# PowerSwitchV1.net
KiCad netlist of a schematic drawn in EAGLE
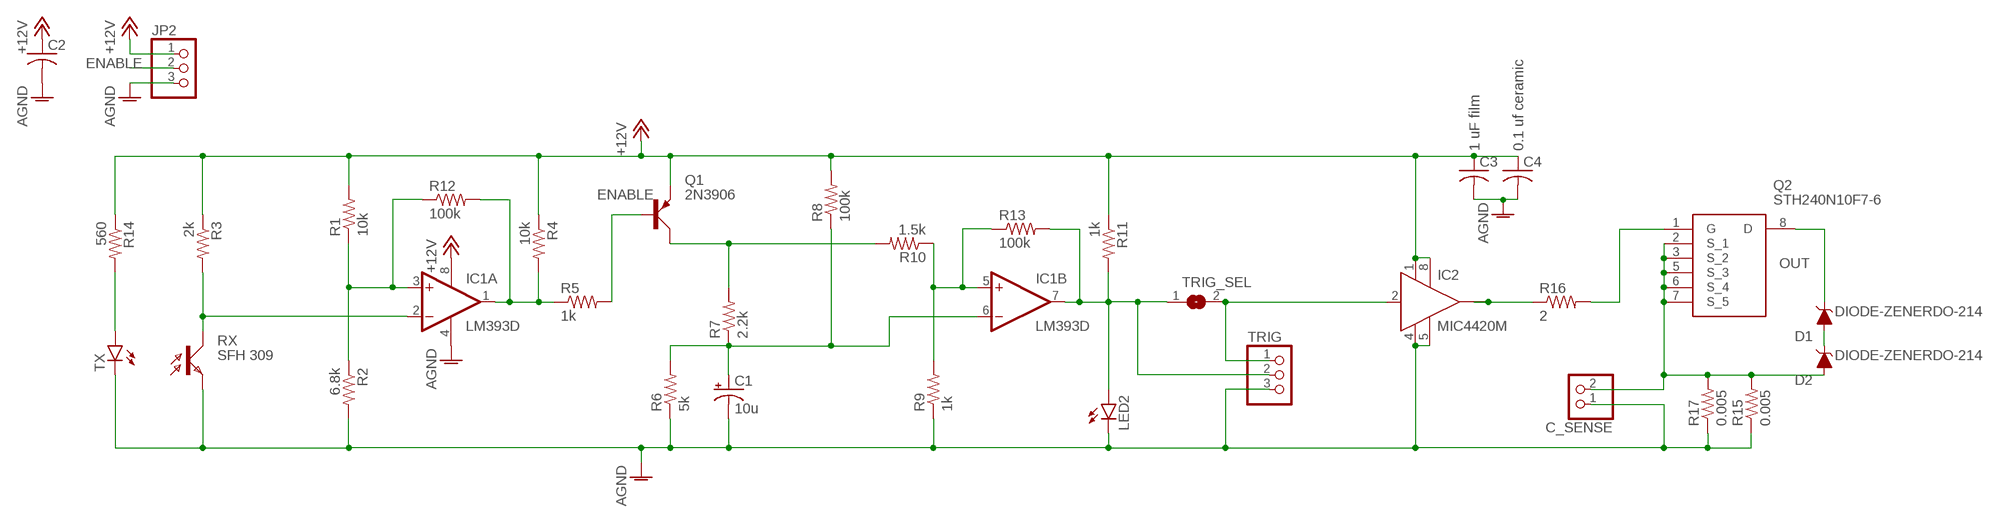
[diagram p0: schematic, sheet 1]

(export (version "E")
  (design (tool "Eeschema 10.0.6"))
  (components
    (comp (ref "C1")
      (value "10u")
      (footprint "eagle-import:TT2D6")
      (libsource (lib "eagle-import") (part "CPOL-USTT2D6"))
    )
    (comp (ref "C2")
      (value "C-US050-050X075")
      (footprint "eagle-import:C050-050X075")
      (libsource (lib "eagle-import") (part "C-US050-050X075"))
    )
    (comp (ref "C3")
      (value "1 uF film")
      (footprint "eagle-import:C050-045X075")
      (libsource (lib "eagle-import") (part "C-US050-045X075"))
    )
    (comp (ref "C4")
      (value "0.1 uf ceramic")
      (footprint "eagle-import:C025-030X050")
      (libsource (lib "eagle-import") (part "C-US025-030X050"))
    )
    (comp (ref "C_SENSE")
      (value "PINHD-1X2")
      (footprint "eagle-import:1X02")
      (libsource (lib "eagle-import") (part "PINHD-1X2"))
    )
    (comp (ref "D1")
      (value "DIODE-ZENERDO-214")
      (footprint "eagle-import:SMA-DIODE")
      (libsource (lib "eagle-import") (part "DIODE-ZENERDO-214"))
    )
    (comp (ref "D2")
      (value "DIODE-ZENERDO-214")
      (footprint "eagle-import:SMA-DIODE")
      (libsource (lib "eagle-import") (part "DIODE-ZENERDO-214"))
    )
    (comp (ref "IC1")
      (value "LM393D")
      (footprint "eagle-import:SO08")
      (libsource (lib "eagle-import") (part "LM393D"))
    )
    (comp (ref "IC2")
      (value "MIC4420M")
      (footprint "eagle-import:SO-08")
      (libsource (lib "eagle-import") (part "MIC4420M"))
    )
    (comp (ref "JP2")
      (value "PINHD-1X3")
      (footprint "eagle-import:1X03")
      (libsource (lib "eagle-import") (part "PINHD-1X3"))
    )
    (comp (ref "LED2")
      (value "LEDCHIPLED_0603")
      (footprint "eagle-import:CHIPLED_0603")
      (libsource (lib "eagle-import") (part "LEDCHIPLED_0603"))
    )
    (comp (ref "Q1")
      (value "2N3906")
      (footprint "eagle-import:TO92D")
      (libsource (lib "eagle-import") (part "2N3906"))
    )
    (comp (ref "Q2")
      (value "STH240N10F7-6")
      (footprint "eagle-import:H2PAK-6_1")
      (fields (field (name "MOUSER_PART_NUMBER") "511-STH240N10F7-6"))
      (libsource (lib "eagle-import") (part "STH240N10F7-6"))
    )
    (comp (ref "R1")
      (value "10k")
      (footprint "eagle-import:R0603")
      (libsource (lib "eagle-import") (part "R-US_R0603"))
    )
    (comp (ref "R2")
      (value "6.8k")
      (footprint "eagle-import:R0603")
      (libsource (lib "eagle-import") (part "R-US_R0603"))
    )
    (comp (ref "R3")
      (value "2k")
      (footprint "eagle-import:R0603")
      (libsource (lib "eagle-import") (part "R-US_R0603"))
    )
    (comp (ref "R4")
      (value "10k")
      (footprint "eagle-import:R0603")
      (libsource (lib "eagle-import") (part "R-US_R0603"))
    )
    (comp (ref "R5")
      (value "1k")
      (footprint "eagle-import:R0603")
      (libsource (lib "eagle-import") (part "R-US_R0603"))
    )
    (comp (ref "R6")
      (value "5k")
      (footprint "eagle-import:R0603")
      (libsource (lib "eagle-import") (part "R-US_R0603"))
    )
    (comp (ref "R7")
      (value "2.2k")
      (footprint "eagle-import:R0603")
      (libsource (lib "eagle-import") (part "R-US_R0603"))
    )
    (comp (ref "R8")
      (value "100k")
      (footprint "eagle-import:R0603")
      (libsource (lib "eagle-import") (part "R-US_R0603"))
    )
    (comp (ref "R9")
      (value "1k")
      (footprint "eagle-import:R0603")
      (libsource (lib "eagle-import") (part "R-US_R0603"))
    )
    (comp (ref "R10")
      (value "1.5k")
      (footprint "eagle-import:R0603")
      (libsource (lib "eagle-import") (part "R-US_R0603"))
    )
    (comp (ref "R11")
      (value "1k")
      (footprint "eagle-import:R0603")
      (libsource (lib "eagle-import") (part "R-US_R0603"))
    )
    (comp (ref "R12")
      (value "100k")
      (footprint "eagle-import:R0603")
      (libsource (lib "eagle-import") (part "R-US_R0603"))
    )
    (comp (ref "R13")
      (value "100k")
      (footprint "eagle-import:R0603")
      (libsource (lib "eagle-import") (part "R-US_R0603"))
    )
    (comp (ref "R14")
      (value "560")
      (footprint "eagle-import:R0603")
      (libsource (lib "eagle-import") (part "R-US_R0603"))
    )
    (comp (ref "R15")
      (value "0.005")
      (footprint "eagle-import:R1206")
      (libsource (lib "eagle-import") (part "R-US_R1206"))
    )
    (comp (ref "R16")
      (value "2")
      (footprint "eagle-import:M0805")
      (libsource (lib "eagle-import") (part "R-US_M0805"))
    )
    (comp (ref "R17")
      (value "0.005")
      (footprint "eagle-import:R1206")
      (libsource (lib "eagle-import") (part "R-US_R1206"))
    )
    (comp (ref "RX")
      (value "SFH 309")
      (footprint "eagle-import:BPX81")
      (libsource (lib "eagle-import") (part "BPX81"))
    )
    (comp (ref "TRIG")
      (value "PINHD-1X3")
      (footprint "eagle-import:1X03")
      (libsource (lib "eagle-import") (part "PINHD-1X3"))
    )
    (comp (ref "TRIG_SEL")
      (value "SJ")
      (footprint "eagle-import:SJ")
      (libsource (lib "eagle-import") (part "SJ"))
    )
    (comp (ref "TX")
      (value "LED3MM")
      (footprint "eagle-import:LED3MM")
      (libsource (lib "eagle-import") (part "LED3MM"))
    )
  )
  (nets
    (net (code "1") (name "+12V") (class "Default")
      (node (ref "C2") (pin "1") (pinfunction "1_1") (pintype "passive"))
      (node (ref "C3") (pin "1") (pinfunction "1_1") (pintype "passive"))
      (node (ref "C4") (pin "1") (pinfunction "1_1") (pintype "passive"))
      (node (ref "IC1") (pin "8") (pinfunction "V+_8") (pintype "power_in"))
      (node (ref "IC2") (pin "1") (pinfunction "VS_1") (pintype "power_in"))
      (node (ref "IC2") (pin "8") (pinfunction "VS1_8") (pintype "power_in"))
      (node (ref "JP2") (pin "1") (pinfunction "1_1") (pintype "passive"))
      (node (ref "Q1") (pin "E") (pinfunction "E_E") (pintype "passive"))
      (node (ref "R1") (pin "2") (pinfunction "2_2") (pintype "passive"))
      (node (ref "R11") (pin "1") (pinfunction "1_1") (pintype "passive"))
      (node (ref "R14") (pin "1") (pinfunction "1_1") (pintype "passive"))
      (node (ref "R3") (pin "1") (pinfunction "1_1") (pintype "passive"))
      (node (ref "R4") (pin "1") (pinfunction "1_1") (pintype "passive"))
      (node (ref "R8") (pin "2") (pinfunction "2_2") (pintype "passive"))
    )
    (net (code "2") (name "/ENABLE") (class "Default")
      (node (ref "JP2") (pin "2") (pinfunction "2_2") (pintype "passive"))
      (node (ref "Q1") (pin "B") (pinfunction "B_B") (pintype "passive"))
      (node (ref "R5") (pin "2") (pinfunction "2_2") (pintype "passive"))
    )
    (net (code "3") (name "/OUT") (class "Default")
      (node (ref "D1") (pin "C") (pinfunction "C_C") (pintype "passive"))
      (node (ref "Q2") (pin "8") (pinfunction "D_8") (pintype "bidirectional"))
    )
    (net (code "4") (name "AGND") (class "Default")
      (node (ref "C1") (pin "-") (pinfunction "-_-") (pintype "passive"))
      (node (ref "C2") (pin "2") (pinfunction "2_2") (pintype "passive"))
      (node (ref "C3") (pin "2") (pinfunction "2_2") (pintype "passive"))
      (node (ref "C4") (pin "2") (pinfunction "2_2") (pintype "passive"))
      (node (ref "C_SENSE") (pin "1") (pinfunction "1_1") (pintype "passive"))
      (node (ref "IC1") (pin "4") (pinfunction "V-_4") (pintype "power_in"))
      (node (ref "IC2") (pin "4") (pinfunction "GND_4") (pintype "power_in"))
      (node (ref "IC2") (pin "5") (pinfunction "GND1_5") (pintype "power_in"))
      (node (ref "JP2") (pin "3") (pinfunction "3_3") (pintype "passive"))
      (node (ref "LED2") (pin "C") (pinfunction "C_C") (pintype "passive"))
      (node (ref "R15") (pin "1") (pinfunction "1_1") (pintype "passive"))
      (node (ref "R17") (pin "1") (pinfunction "1_1") (pintype "passive"))
      (node (ref "R2") (pin "2") (pinfunction "2_2") (pintype "passive"))
      (node (ref "R6") (pin "1") (pinfunction "1_1") (pintype "passive"))
      (node (ref "R9") (pin "1") (pinfunction "1_1") (pintype "passive"))
      (node (ref "RX") (pin "E") (pinfunction "E_E") (pintype "passive"))
      (node (ref "TRIG") (pin "3") (pinfunction "3_3") (pintype "passive"))
      (node (ref "TX") (pin "K") (pinfunction "C_K") (pintype "passive"))
    )
    (net (code "5") (name "Net-(D1-PadA)") (class "Default")
      (node (ref "D1") (pin "A") (pinfunction "A_A") (pintype "passive"))
      (node (ref "D2") (pin "C") (pinfunction "C_C") (pintype "passive"))
    )
    (net (code "6") (name "Net-(IC1A-+IN)") (class "Default")
      (node (ref "IC1") (pin "3") (pinfunction "+IN_3") (pintype "input"))
      (node (ref "R1") (pin "1") (pinfunction "1_1") (pintype "passive"))
      (node (ref "R12") (pin "1") (pinfunction "1_1") (pintype "passive"))
      (node (ref "R2") (pin "1") (pinfunction "1_1") (pintype "passive"))
    )
    (net (code "7") (name "Net-(IC1A--IN)") (class "Default")
      (node (ref "IC1") (pin "2") (pinfunction "-IN_2") (pintype "input"))
      (node (ref "R3") (pin "2") (pinfunction "2_2") (pintype "passive"))
      (node (ref "RX") (pin "C") (pinfunction "C_C") (pintype "passive"))
    )
    (net (code "8") (name "Net-(IC1A-OUT)") (class "Default")
      (node (ref "IC1") (pin "1") (pinfunction "OUT_1") (pintype "output"))
      (node (ref "R12") (pin "2") (pinfunction "2_2") (pintype "passive"))
      (node (ref "R4") (pin "2") (pinfunction "2_2") (pintype "passive"))
      (node (ref "R5") (pin "1") (pinfunction "1_1") (pintype "passive"))
    )
    (net (code "9") (name "Net-(IC1B-+IN)") (class "Default")
      (node (ref "IC1") (pin "5") (pinfunction "+IN_5") (pintype "input"))
      (node (ref "R10") (pin "1") (pinfunction "1_1") (pintype "passive"))
      (node (ref "R13") (pin "1") (pinfunction "1_1") (pintype "passive"))
      (node (ref "R9") (pin "2") (pinfunction "2_2") (pintype "passive"))
    )
    (net (code "10") (name "Net-(IC1B--IN)") (class "Default")
      (node (ref "C1") (pin "+") (pinfunction "+_+") (pintype "passive"))
      (node (ref "IC1") (pin "6") (pinfunction "-IN_6") (pintype "input"))
      (node (ref "R6") (pin "2") (pinfunction "2_2") (pintype "passive"))
      (node (ref "R7") (pin "1") (pinfunction "1_1") (pintype "passive"))
      (node (ref "R8") (pin "1") (pinfunction "1_1") (pintype "passive"))
    )
    (net (code "11") (name "Net-(IC1B-OUT)") (class "Default")
      (node (ref "IC1") (pin "7") (pinfunction "OUT_7") (pintype "output"))
      (node (ref "LED2") (pin "A") (pinfunction "A_A") (pintype "passive"))
      (node (ref "R11") (pin "2") (pinfunction "2_2") (pintype "passive"))
      (node (ref "R13") (pin "2") (pinfunction "2_2") (pintype "passive"))
      (node (ref "TRIG") (pin "2") (pinfunction "2_2") (pintype "passive"))
      (node (ref "TRIG_SEL") (pin "1") (pinfunction "1_1") (pintype "passive"))
    )
    (net (code "12") (name "Net-(IC2-IN)") (class "Default")
      (node (ref "IC2") (pin "2") (pinfunction "IN_2") (pintype "input"))
      (node (ref "TRIG") (pin "1") (pinfunction "1_1") (pintype "passive"))
      (node (ref "TRIG_SEL") (pin "2") (pinfunction "2_2") (pintype "passive"))
    )
    (net (code "13") (name "Net-(IC2-OUT-Pad6)") (class "Default")
      (node (ref "IC2") (pin "6") (pinfunction "OUT_6") (pintype "passive"))
      (node (ref "IC2") (pin "7") (pinfunction "OUT_7") (pintype "passive"))
      (node (ref "R16") (pin "1") (pinfunction "1_1") (pintype "passive"))
    )
    (net (code "14") (name "Net-(Q1-PadC)") (class "Default")
      (node (ref "Q1") (pin "C") (pinfunction "C_C") (pintype "passive"))
      (node (ref "R10") (pin "2") (pinfunction "2_2") (pintype "passive"))
      (node (ref "R7") (pin "2") (pinfunction "2_2") (pintype "passive"))
    )
    (net (code "15") (name "Net-(Q2-G)") (class "Default")
      (node (ref "Q2") (pin "1") (pinfunction "G_1") (pintype "bidirectional"))
      (node (ref "R16") (pin "2") (pinfunction "2_2") (pintype "passive"))
    )
    (net (code "16") (name "Net-(Q2-S_1)") (class "Default")
      (node (ref "C_SENSE") (pin "2") (pinfunction "2_2") (pintype "passive"))
      (node (ref "D2") (pin "A") (pinfunction "A_A") (pintype "passive"))
      (node (ref "Q2") (pin "2") (pinfunction "S_1_2") (pintype "bidirectional"))
      (node (ref "Q2") (pin "3") (pinfunction "S_2_3") (pintype "bidirectional"))
      (node (ref "Q2") (pin "5") (pinfunction "S_3_5") (pintype "bidirectional"))
      (node (ref "Q2") (pin "6") (pinfunction "S_4_6") (pintype "bidirectional"))
      (node (ref "Q2") (pin "7") (pinfunction "S_5_7") (pintype "bidirectional"))
      (node (ref "R15") (pin "2") (pinfunction "2_2") (pintype "passive"))
      (node (ref "R17") (pin "2") (pinfunction "2_2") (pintype "passive"))
    )
    (net (code "17") (name "Net-(R14-Pad2)") (class "Default")
      (node (ref "R14") (pin "2") (pinfunction "2_2") (pintype "passive"))
      (node (ref "TX") (pin "A") (pinfunction "A_A") (pintype "passive"))
    )
  )
)
